# MAX30208_HSP3_DEMO_B.net
KiCad netlist of a schematic drawn in Altium Designer
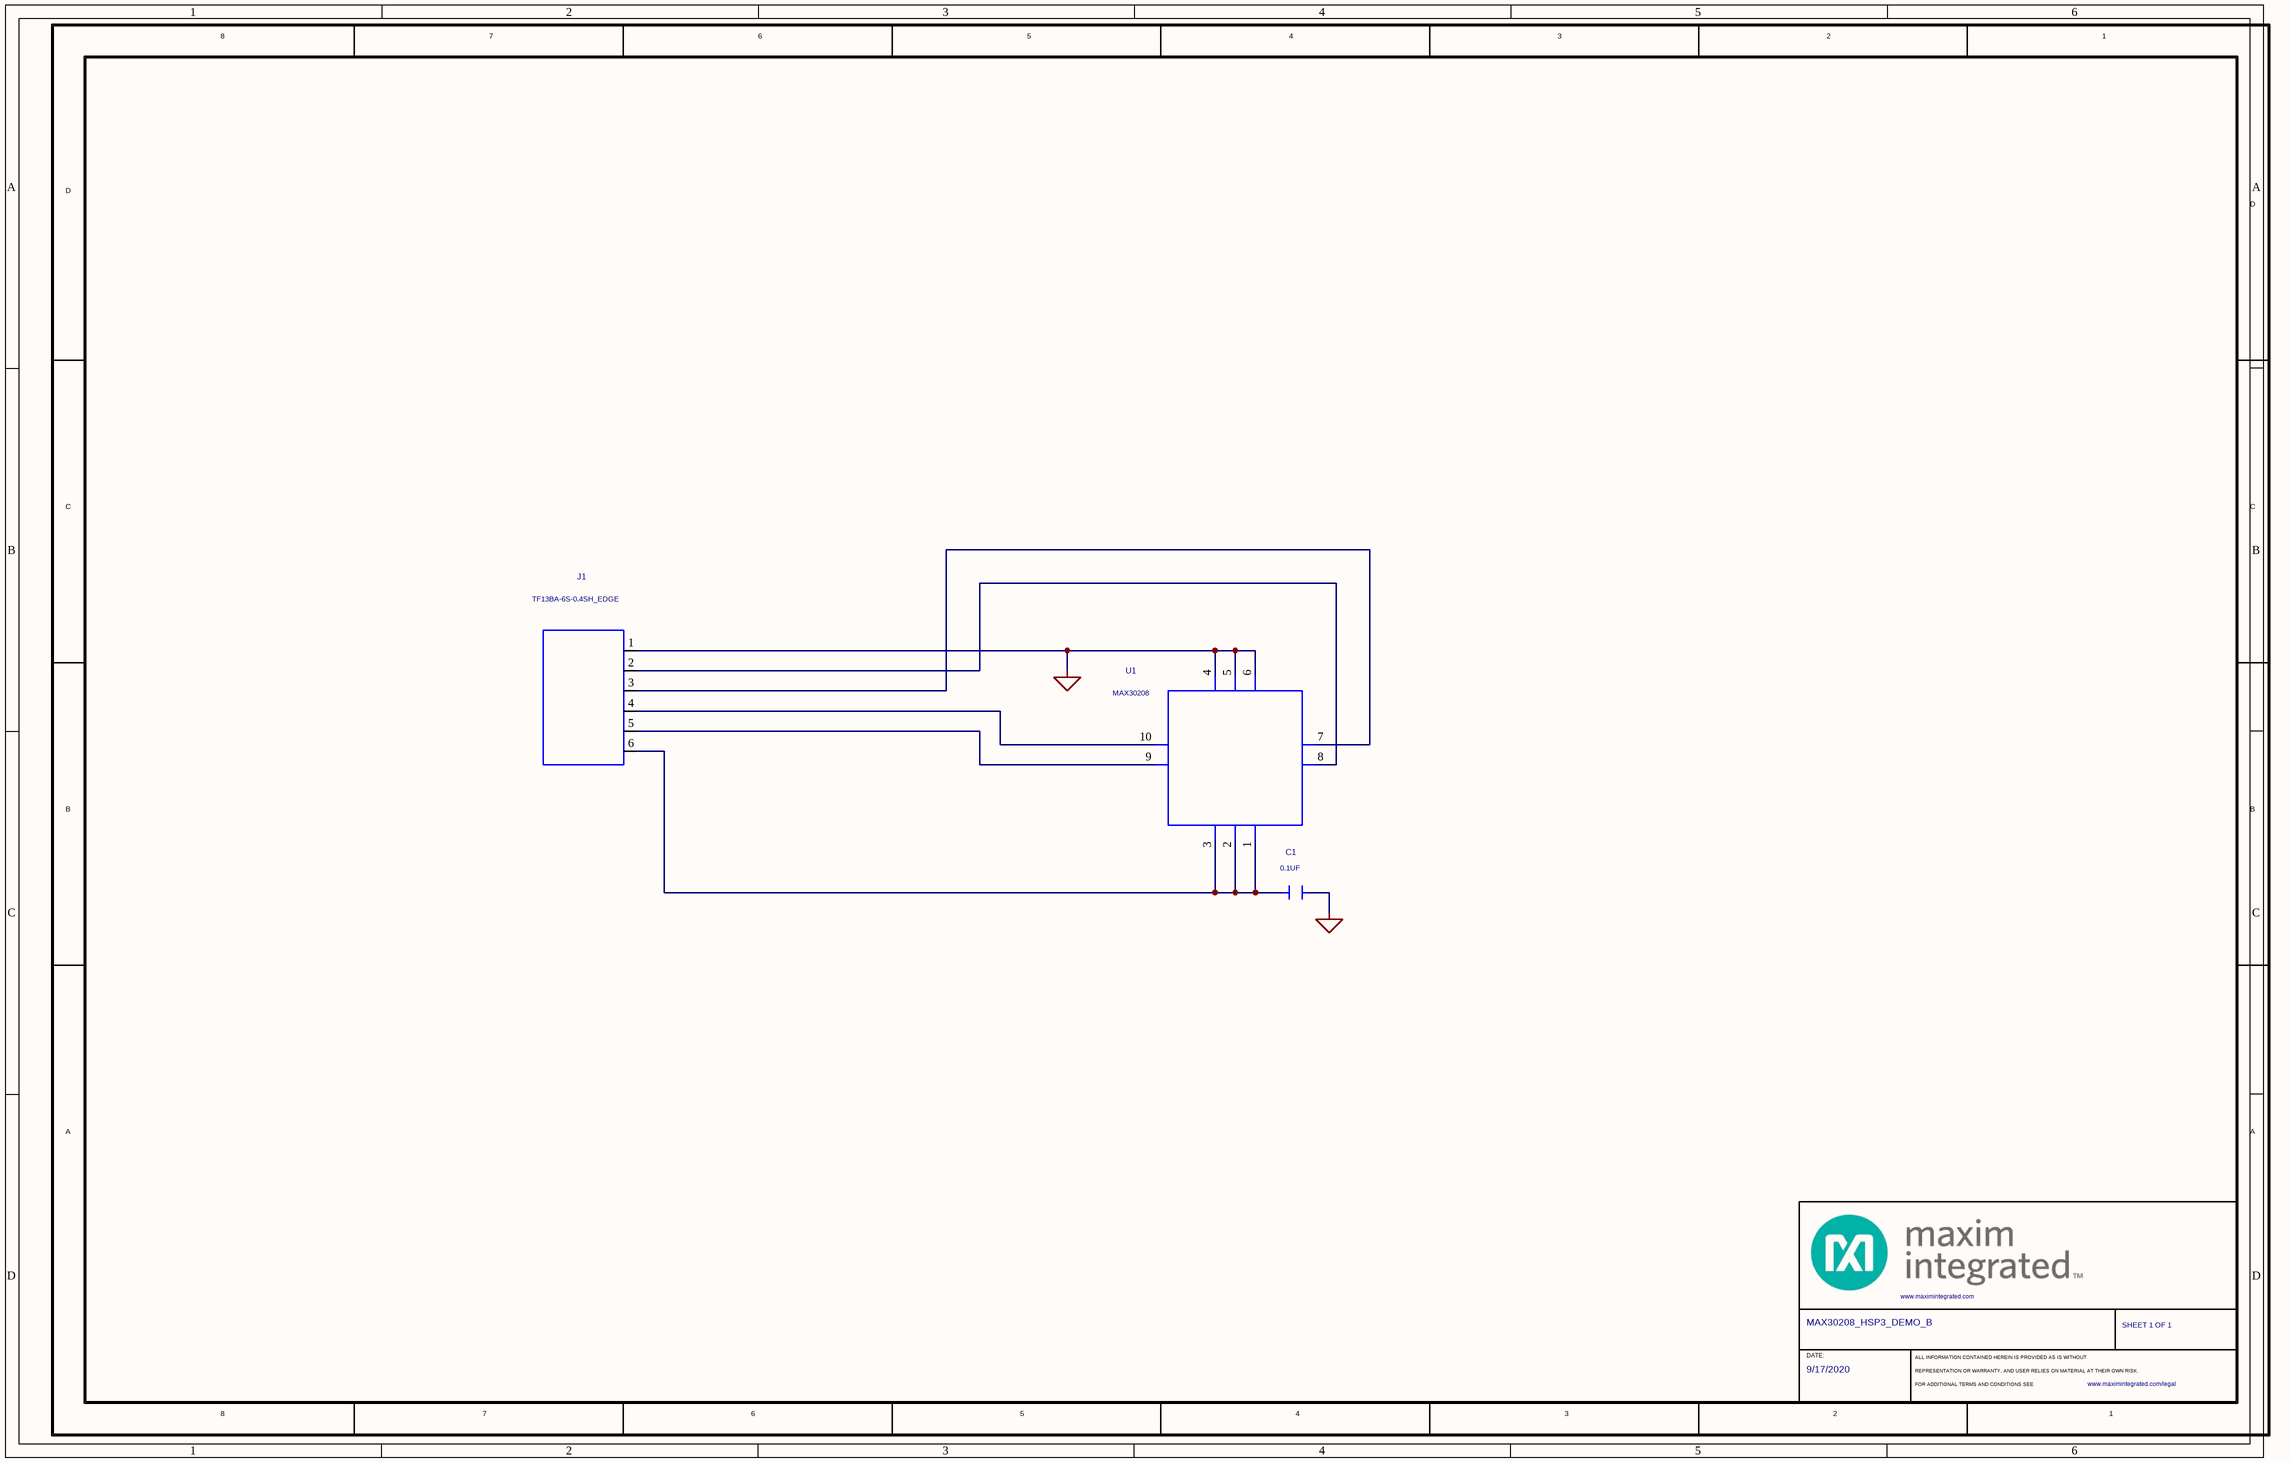
[diagram p0: MAX30208_HSP3_DEMO_B.SchDoc]

(export (version "E")
  (design (tool "Eeschema 10.0.6"))
  (components
    (comp (ref "*")
      (value "MAXIM_B_SIZE_CF")
      (fields
        (field (name "CUSTOM_TXT_CDS21") "SHEET 1 OF 1")
        (field (name "PROJECT_TITLE") "MAX30208_HSP3_DEMO_B")
        (field (name "LEAGAL_WEBLINK") "www.maximintegrated.com/legal")
        (field (name "WEBLINK1") "www.maximintegrated.com")
        (field (name "DATE") "9/17/2020")
      )
      (libsource (lib "*") (part "MAXIM_B_SIZE_CF"))
    )
    (comp (ref "C1")
      (value "0.1UF")
      (footprint "CAPC0603X33M")
      (description "CAP; SMT (0201); 0.1UF; 10%; 25V; X6S; CERAMIC")
      (fields (field (name "MFG_PART_NUMBER") "GRM033C81E104KE14") (field (name "TOLERANCE") "10%"))
      (libsource (lib "*") (part "CAP_NP"))
    )
    (comp (ref "J1")
      (value "TF13BA-6S-0.4SH_EDGE")
      (footprint "HRSC_TF13BA-6S-0_4SH_EDGE")
      (fields (field (name "MANUFACTURER") "HIROSE ELECTRIC CO LTD"))
      (libsource (lib "*") (part "TF13BA-6S"))
    )
    (comp (ref "U1")
      (value "MAX30208")
      (footprint "MAX_90-100101_1-10")
      (description "EVKIT PART - IC; MAX30208; PACKAGE OUTLINE DRAWING: 21-100265; LGA10")
      (fields (field (name "MANUFACTURER") "MAXIM"))
      (libsource (lib "*") (part "EK_MAX30208"))
    )
  )
  (nets
    (net (code "1") (name "GND_SIGNAL") (class "Default")
      (node (ref "C1") (pin "2") (pinfunction "2_2") (pintype "bidirectional"))
      (node (ref "J1") (pin "1") (pinfunction "1_1") (pintype "bidirectional"))
      (node (ref "U1") (pin "4") (pinfunction "4_4") (pintype "bidirectional"))
      (node (ref "U1") (pin "5") (pinfunction "5_5") (pintype "bidirectional"))
      (node (ref "U1") (pin "6") (pinfunction "6_6") (pintype "bidirectional"))
    )
    (net (code "2") (name "Net-(C1-Pad1)") (class "Default")
      (node (ref "C1") (pin "1") (pinfunction "1_1") (pintype "bidirectional"))
      (node (ref "J1") (pin "6") (pinfunction "6_6") (pintype "bidirectional"))
      (node (ref "U1") (pin "1") (pinfunction "1_1") (pintype "bidirectional"))
      (node (ref "U1") (pin "2") (pinfunction "2_2") (pintype "bidirectional"))
      (node (ref "U1") (pin "3") (pinfunction "3_3") (pintype "bidirectional"))
    )
    (net (code "3") (name "Net-(J1-Pad2)") (class "Default")
      (node (ref "J1") (pin "2") (pinfunction "2_2") (pintype "bidirectional"))
      (node (ref "U1") (pin "8") (pinfunction "8_8") (pintype "bidirectional"))
    )
    (net (code "4") (name "Net-(J1-Pad3)") (class "Default")
      (node (ref "J1") (pin "3") (pinfunction "3_3") (pintype "bidirectional"))
      (node (ref "U1") (pin "7") (pinfunction "7_7") (pintype "bidirectional"))
    )
    (net (code "5") (name "Net-(J1-Pad4)") (class "Default")
      (node (ref "J1") (pin "4") (pinfunction "4_4") (pintype "bidirectional"))
      (node (ref "U1") (pin "10") (pinfunction "10_10") (pintype "bidirectional"))
    )
    (net (code "6") (name "Net-(J1-Pad5)") (class "Default")
      (node (ref "J1") (pin "5") (pinfunction "5_5") (pintype "bidirectional"))
      (node (ref "U1") (pin "9") (pinfunction "9_9") (pintype "bidirectional"))
    )
  )
)
